# unoshield-v4.net
KiCad netlist of a schematic drawn in EAGLE
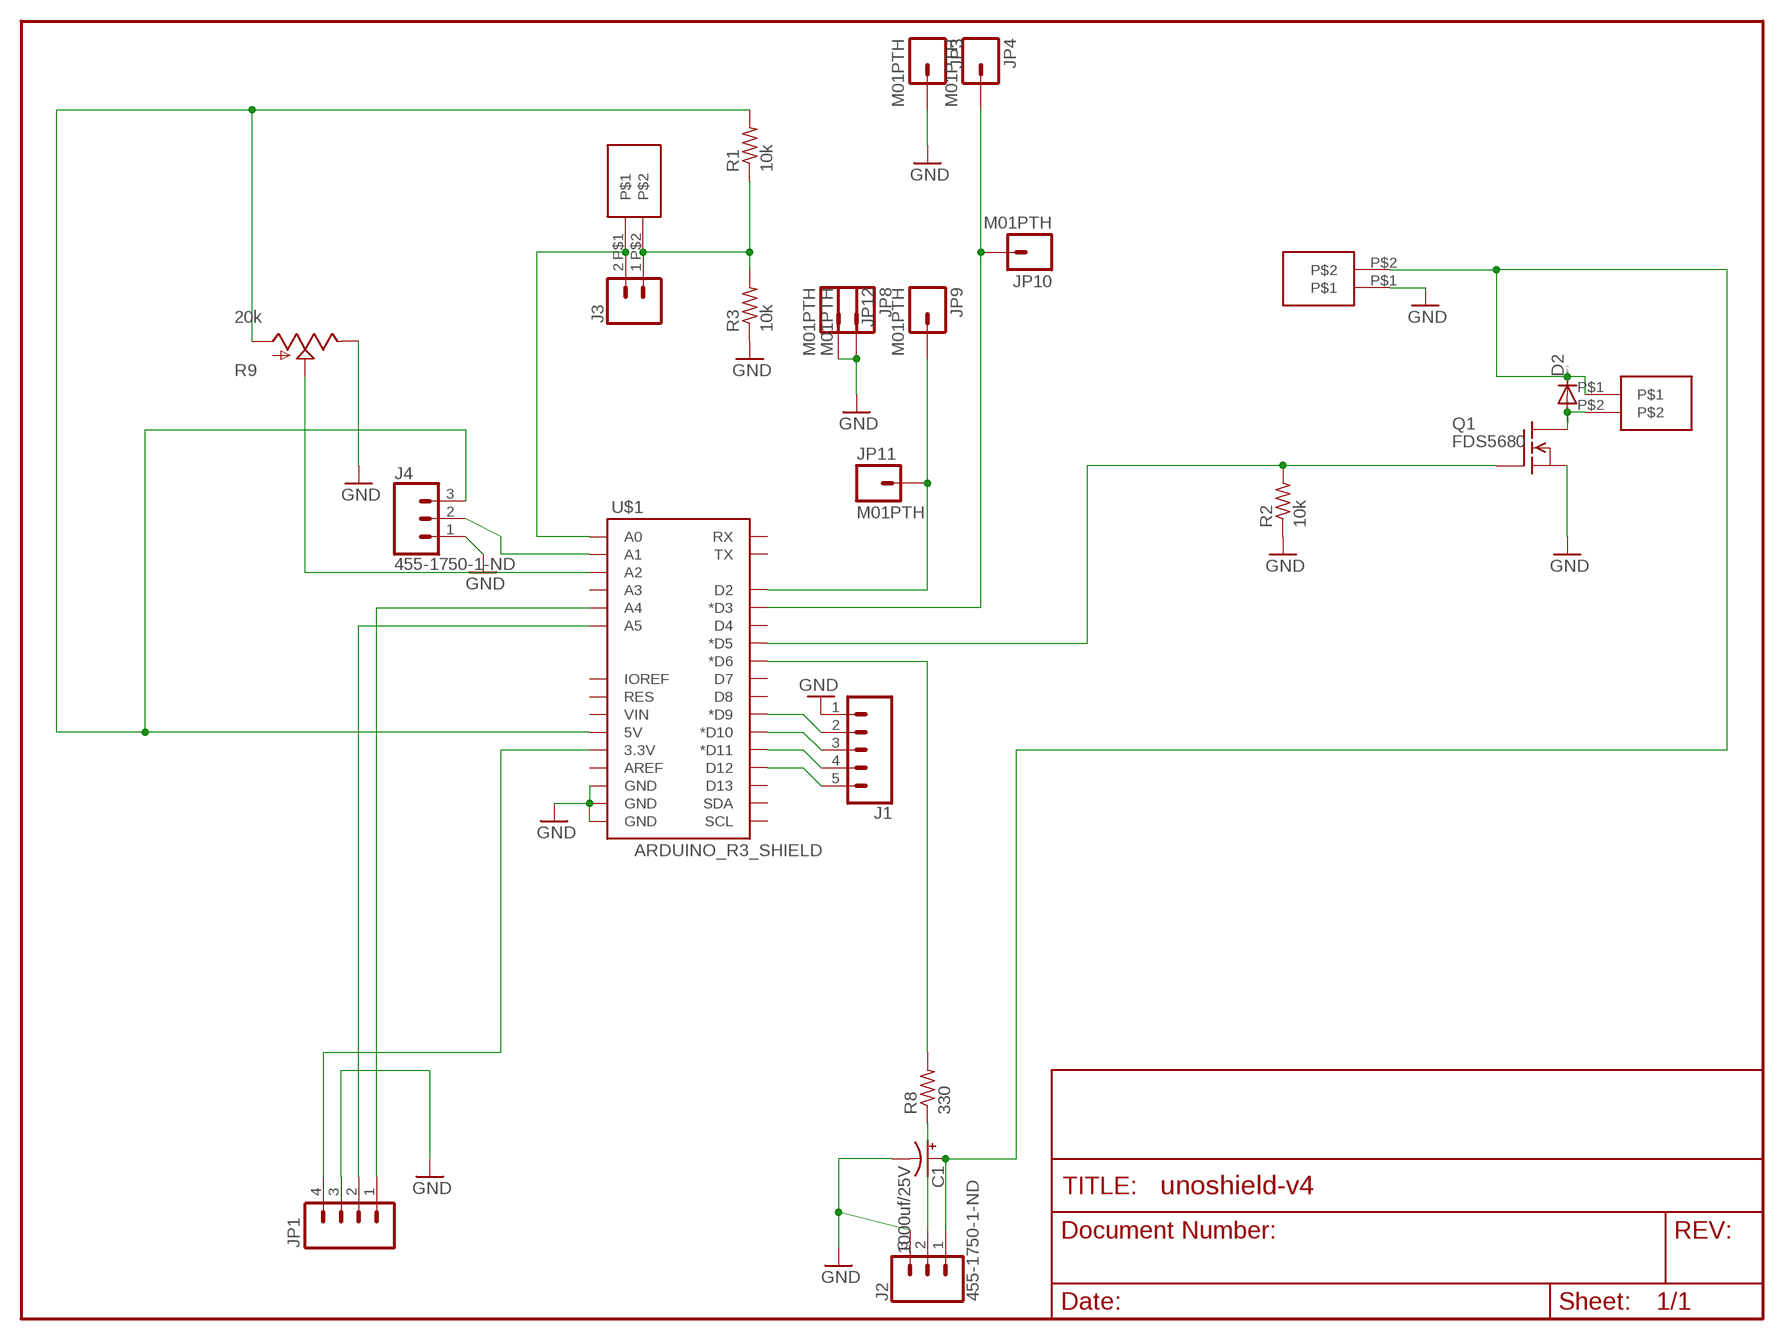
[diagram p0: schematic, sheet 1]

(export (version "E")
  (design (tool "Eeschema 10.0.6"))
  (components
    (comp (ref "C1")
      (value "1000uf/25V")
      (footprint "eagle-import:CPOL-RADIAL-1000UF-25V-KIT")
      (libsource (lib "eagle-import") (part "1000UF-25V(PTH)KIT"))
    )
    (comp (ref "D2")
      (value "DIODE-DO-214AC")
      (footprint "eagle-import:DO-214AC")
      (libsource (lib "eagle-import") (part "DIODE-DO-214AC"))
    )
    (comp (ref "J1")
      (value "CONN_05")
      (footprint "eagle-import:1X05")
      (libsource (lib "eagle-import") (part "CONN_05"))
    )
    (comp (ref "J2")
      (value "455-1750-1-ND")
      (footprint "eagle-import:1X03")
      (libsource (lib "eagle-import") (part "CONN_03"))
    )
    (comp (ref "J3")
      (value "CONN_02")
      (footprint "eagle-import:1X02")
      (libsource (lib "eagle-import") (part "CONN_02"))
    )
    (comp (ref "J4")
      (value "455-1750-1-ND")
      (footprint "eagle-import:1X03")
      (libsource (lib "eagle-import") (part "CONN_03"))
    )
    (comp (ref "JP1")
      (value "M04PTH")
      (footprint "eagle-import:1X04")
      (libsource (lib "eagle-import") (part "M04PTH"))
    )
    (comp (ref "JP3")
      (value "M01PTH")
      (footprint "eagle-import:1X01")
      (libsource (lib "eagle-import") (part "M01PTH"))
    )
    (comp (ref "JP4")
      (value "M01PTH")
      (footprint "eagle-import:1X01")
      (libsource (lib "eagle-import") (part "M01PTH"))
    )
    (comp (ref "JP8")
      (value "M01PTH")
      (footprint "eagle-import:1X01")
      (libsource (lib "eagle-import") (part "M01PTH"))
    )
    (comp (ref "JP9")
      (value "M01PTH")
      (footprint "eagle-import:1X01")
      (libsource (lib "eagle-import") (part "M01PTH"))
    )
    (comp (ref "JP10")
      (value "M01PTH")
      (footprint "eagle-import:1X01")
      (libsource (lib "eagle-import") (part "M01PTH"))
    )
    (comp (ref "JP11")
      (value "M01PTH")
      (footprint "eagle-import:1X01")
      (libsource (lib "eagle-import") (part "M01PTH"))
    )
    (comp (ref "JP12")
      (value "M01PTH")
      (footprint "eagle-import:1X01")
      (libsource (lib "eagle-import") (part "M01PTH"))
    )
    (comp (ref "Q1")
      (value "FDS5680")
      (footprint "eagle-import:SO-8")
      (libsource (lib "eagle-import") (part "FDS5680"))
    )
    (comp (ref "R1")
      (value "10k")
      (footprint "eagle-import:R0603")
      (libsource (lib "eagle-import") (part "R-US_R0603"))
    )
    (comp (ref "R2")
      (value "10k")
      (footprint "eagle-import:R0603")
      (libsource (lib "eagle-import") (part "R-US_R0603"))
    )
    (comp (ref "R3")
      (value "10k")
      (footprint "eagle-import:R0603")
      (libsource (lib "eagle-import") (part "R-US_R0603"))
    )
    (comp (ref "R8")
      (value "330")
      (footprint "eagle-import:R0603")
      (libsource (lib "eagle-import") (part "R-US_R0603"))
    )
    (comp (ref "R9")
      (value "20k")
      (footprint "eagle-import:ALPS_POT_KIT")
      (libsource (lib "eagle-import") (part "POTALPS-KIT"))
    )
    (comp (ref "U$1")
      (value "ARDUINO_R3_SHIELD")
      (footprint "eagle-import:UNO_R3_SHIELD")
      (libsource (lib "eagle-import") (part "ARDUINO_R3_SHIELD"))
    )
    (comp (ref "U$6")
      (value "SPRING-TERMINAL")
      (footprint "eagle-import:SPRING-TERMINAL")
      (libsource (lib "eagle-import") (part "SPRING-TERMINAL"))
    )
    (comp (ref "X1")
      (value "SPRING-TERMINAL")
      (footprint "eagle-import:SPRING-TERMINAL")
      (libsource (lib "eagle-import") (part "SPRING-TERMINAL"))
    )
    (comp (ref "X2")
      (value "SPRING-TERMINAL")
      (footprint "eagle-import:SPRING-TERMINAL")
      (libsource (lib "eagle-import") (part "SPRING-TERMINAL"))
    )
  )
  (nets
    (net (code "1") (name "GND") (class "Default")
      (node (ref "C1") (pin "-") (pinfunction "-_-") (pintype "passive"))
      (node (ref "J1") (pin "1") (pinfunction "1_1") (pintype "passive"))
      (node (ref "J2") (pin "3") (pinfunction "3_3") (pintype "passive"))
      (node (ref "J4") (pin "1") (pinfunction "1_1") (pintype "passive"))
      (node (ref "JP1") (pin "3") (pinfunction "3_3") (pintype "passive"))
      (node (ref "JP12") (pin "1") (pinfunction "1_1") (pintype "passive"))
      (node (ref "JP3") (pin "1") (pinfunction "1_1") (pintype "passive"))
      (node (ref "JP8") (pin "1") (pinfunction "1_1") (pintype "passive"))
      (node (ref "Q1") (pin "1") (pinfunction "S_1") (pintype "passive"))
      (node (ref "Q1") (pin "2") (pinfunction "S_2") (pintype "passive"))
      (node (ref "Q1") (pin "3") (pinfunction "S_3") (pintype "passive"))
      (node (ref "R2") (pin "1") (pinfunction "1_1") (pintype "passive"))
      (node (ref "R3") (pin "1") (pinfunction "1_1") (pintype "passive"))
      (node (ref "R9") (pin "P$1") (pinfunction "E_P$1") (pintype "passive"))
      (node (ref "U$1") (pin "GND@0") (pinfunction "GND_GND@0") (pintype "bidirectional"))
      (node (ref "U$1") (pin "GND@1") (pinfunction "GND_GND@1") (pintype "bidirectional"))
      (node (ref "U$1") (pin "GND@2") (pinfunction "GND_GND@2") (pintype "bidirectional"))
      (node (ref "X1") (pin "P$1") (pinfunction "P$1_P$1") (pintype "bidirectional"))
    )
    (net (code "2") (name "Net-(C1-Pad+)") (class "Default")
      (node (ref "C1") (pin "+") (pinfunction "+_+") (pintype "passive"))
      (node (ref "D2") (pin "C") (pinfunction "C_C") (pintype "passive"))
      (node (ref "J2") (pin "1") (pinfunction "1_1") (pintype "passive"))
      (node (ref "U$6") (pin "P$1") (pinfunction "P$1_P$1") (pintype "bidirectional"))
      (node (ref "X1") (pin "P$2") (pinfunction "P$2_P$2") (pintype "bidirectional"))
    )
    (net (code "3") (name "Net-(D2-PadA)") (class "Default")
      (node (ref "D2") (pin "A") (pinfunction "A_A") (pintype "passive"))
      (node (ref "Q1") (pin "5") (pinfunction "D_5") (pintype "passive"))
      (node (ref "Q1") (pin "6") (pinfunction "D_6") (pintype "passive"))
      (node (ref "Q1") (pin "7") (pinfunction "D_7") (pintype "passive"))
      (node (ref "Q1") (pin "8") (pinfunction "D_8") (pintype "passive"))
      (node (ref "U$6") (pin "P$2") (pinfunction "P$2_P$2") (pintype "bidirectional"))
    )
    (net (code "4") (name "Net-(J1-Pad5)") (class "Default")
      (node (ref "J1") (pin "5") (pinfunction "5_5") (pintype "passive"))
      (node (ref "U$1") (pin "D12") (pinfunction "D12_D12") (pintype "bidirectional"))
    )
    (net (code "5") (name "Net-(J2-Pad2)") (class "Default")
      (node (ref "J2") (pin "2") (pinfunction "2_2") (pintype "passive"))
      (node (ref "R8") (pin "1") (pinfunction "1_1") (pintype "passive"))
    )
    (net (code "6") (name "Net-(J3-Pad1)") (class "Default")
      (node (ref "J3") (pin "1") (pinfunction "1_1") (pintype "passive"))
      (node (ref "R1") (pin "1") (pinfunction "1_1") (pintype "passive"))
      (node (ref "R3") (pin "2") (pinfunction "2_2") (pintype "passive"))
      (node (ref "X2") (pin "P$2") (pinfunction "P$2_P$2") (pintype "bidirectional"))
    )
    (net (code "7") (name "Net-(J3-Pad2)") (class "Default")
      (node (ref "J3") (pin "2") (pinfunction "2_2") (pintype "passive"))
      (node (ref "U$1") (pin "A0") (pinfunction "A0_A0") (pintype "bidirectional"))
      (node (ref "X2") (pin "P$1") (pinfunction "P$1_P$1") (pintype "bidirectional"))
    )
    (net (code "8") (name "Net-(J4-Pad2)") (class "Default")
      (node (ref "J4") (pin "2") (pinfunction "2_2") (pintype "passive"))
      (node (ref "U$1") (pin "A1") (pinfunction "A1_A1") (pintype "bidirectional"))
    )
    (net (code "9") (name "Net-(JP1-Pad1)") (class "Default")
      (node (ref "JP1") (pin "1") (pinfunction "1_1") (pintype "passive"))
      (node (ref "U$1") (pin "A4") (pinfunction "A4_A4") (pintype "bidirectional"))
    )
    (net (code "10") (name "Net-(JP1-Pad2)") (class "Default")
      (node (ref "JP1") (pin "2") (pinfunction "2_2") (pintype "passive"))
      (node (ref "U$1") (pin "A5") (pinfunction "A5_A5") (pintype "bidirectional"))
    )
    (net (code "11") (name "Net-(JP1-Pad4)") (class "Default")
      (node (ref "JP1") (pin "4") (pinfunction "4_4") (pintype "passive"))
      (node (ref "U$1") (pin "3.3V") (pinfunction "3.3V_3.3V") (pintype "bidirectional"))
    )
    (net (code "12") (name "Net-(JP11-Pad1)") (class "Default")
      (node (ref "JP11") (pin "1") (pinfunction "1_1") (pintype "passive"))
      (node (ref "JP9") (pin "1") (pinfunction "1_1") (pintype "passive"))
      (node (ref "U$1") (pin "D2") (pinfunction "D2_D2") (pintype "bidirectional"))
    )
    (net (code "13") (name "Net-(Q1-G)") (class "Default")
      (node (ref "Q1") (pin "4") (pinfunction "G_4") (pintype "passive"))
      (node (ref "R2") (pin "2") (pinfunction "2_2") (pintype "passive"))
      (node (ref "U$1") (pin "D5") (pinfunction "*D5_D5") (pintype "bidirectional"))
    )
    (net (code "14") (name "Net-(R9-A)") (class "Default")
      (node (ref "J4") (pin "3") (pinfunction "3_3") (pintype "passive"))
      (node (ref "R1") (pin "2") (pinfunction "2_2") (pintype "passive"))
      (node (ref "R9") (pin "P$3") (pinfunction "A_P$3") (pintype "passive"))
      (node (ref "U$1") (pin "5V") (pinfunction "5V_5V") (pintype "bidirectional"))
    )
    (net (code "15") (name "Net-(R9-S)") (class "Default")
      (node (ref "R9") (pin "P$2") (pinfunction "S_P$2") (pintype "passive"))
      (node (ref "U$1") (pin "A2") (pinfunction "A2_A2") (pintype "bidirectional"))
    )
    (net (code "16") (name "Net-(U$1-*D3)") (class "Default")
      (node (ref "JP10") (pin "1") (pinfunction "1_1") (pintype "passive"))
      (node (ref "JP4") (pin "1") (pinfunction "1_1") (pintype "passive"))
      (node (ref "U$1") (pin "D3") (pinfunction "*D3_D3") (pintype "bidirectional"))
    )
    (net (code "17") (name "Net-(U$1-*D6)") (class "Default")
      (node (ref "R8") (pin "2") (pinfunction "2_2") (pintype "passive"))
      (node (ref "U$1") (pin "D6") (pinfunction "*D6_D6") (pintype "bidirectional"))
    )
    (net (code "18") (name "Net-(U$1-*D9)") (class "Default")
      (node (ref "J1") (pin "2") (pinfunction "2_2") (pintype "passive"))
      (node (ref "U$1") (pin "D9") (pinfunction "*D9_D9") (pintype "bidirectional"))
    )
    (net (code "19") (name "Net-(U$1-*D10)") (class "Default")
      (node (ref "J1") (pin "3") (pinfunction "3_3") (pintype "passive"))
      (node (ref "U$1") (pin "D10") (pinfunction "*D10_D10") (pintype "bidirectional"))
    )
    (net (code "20") (name "Net-(U$1-*D11)") (class "Default")
      (node (ref "J1") (pin "4") (pinfunction "4_4") (pintype "passive"))
      (node (ref "U$1") (pin "D11") (pinfunction "*D11_D11") (pintype "bidirectional"))
    )
    (net (code "21") (name "unconnected-(U$1-PadA3)") (class "Default")
      (node (ref "U$1") (pin "A3") (pinfunction "A3_A3") (pintype "bidirectional"))
    )
    (net (code "22") (name "unconnected-(U$1-PadAREF)") (class "Default")
      (node (ref "U$1") (pin "AREF") (pinfunction "AREF_AREF") (pintype "bidirectional"))
    )
    (net (code "23") (name "unconnected-(U$1-PadD4)") (class "Default")
      (node (ref "U$1") (pin "D4") (pinfunction "D4_D4") (pintype "bidirectional"))
    )
    (net (code "24") (name "unconnected-(U$1-PadD7)") (class "Default")
      (node (ref "U$1") (pin "D7") (pinfunction "D7_D7") (pintype "bidirectional"))
    )
    (net (code "25") (name "unconnected-(U$1-PadD8)") (class "Default")
      (node (ref "U$1") (pin "D8") (pinfunction "D8_D8") (pintype "bidirectional"))
    )
    (net (code "26") (name "unconnected-(U$1-PadD13)") (class "Default")
      (node (ref "U$1") (pin "D13") (pinfunction "D13_D13") (pintype "bidirectional"))
    )
    (net (code "27") (name "unconnected-(U$1-PadIOREF)") (class "Default")
      (node (ref "U$1") (pin "IOREF") (pinfunction "IOREF_IOREF") (pintype "bidirectional"))
    )
    (net (code "28") (name "unconnected-(U$1-PadRES)") (class "Default")
      (node (ref "U$1") (pin "RES") (pinfunction "RES_RES") (pintype "bidirectional"))
    )
    (net (code "29") (name "unconnected-(U$1-PadRX)") (class "Default")
      (node (ref "U$1") (pin "RX") (pinfunction "RX_RX") (pintype "bidirectional"))
    )
    (net (code "30") (name "unconnected-(U$1-PadSCL)") (class "Default")
      (node (ref "U$1") (pin "SCL") (pinfunction "SCL_SCL") (pintype "bidirectional"))
    )
    (net (code "31") (name "unconnected-(U$1-PadSDA)") (class "Default")
      (node (ref "U$1") (pin "SDA") (pinfunction "SDA_SDA") (pintype "bidirectional"))
    )
    (net (code "32") (name "unconnected-(U$1-PadTX)") (class "Default")
      (node (ref "U$1") (pin "TX") (pinfunction "TX_TX") (pintype "bidirectional"))
    )
    (net (code "33") (name "unconnected-(U$1-PadVIN)") (class "Default")
      (node (ref "U$1") (pin "VIN") (pinfunction "VIN_VIN") (pintype "bidirectional"))
    )
  )
)
